# IoT_6LoWPAN_gateway_v01.net
KiCad netlist of a schematic drawn in Altium Designer
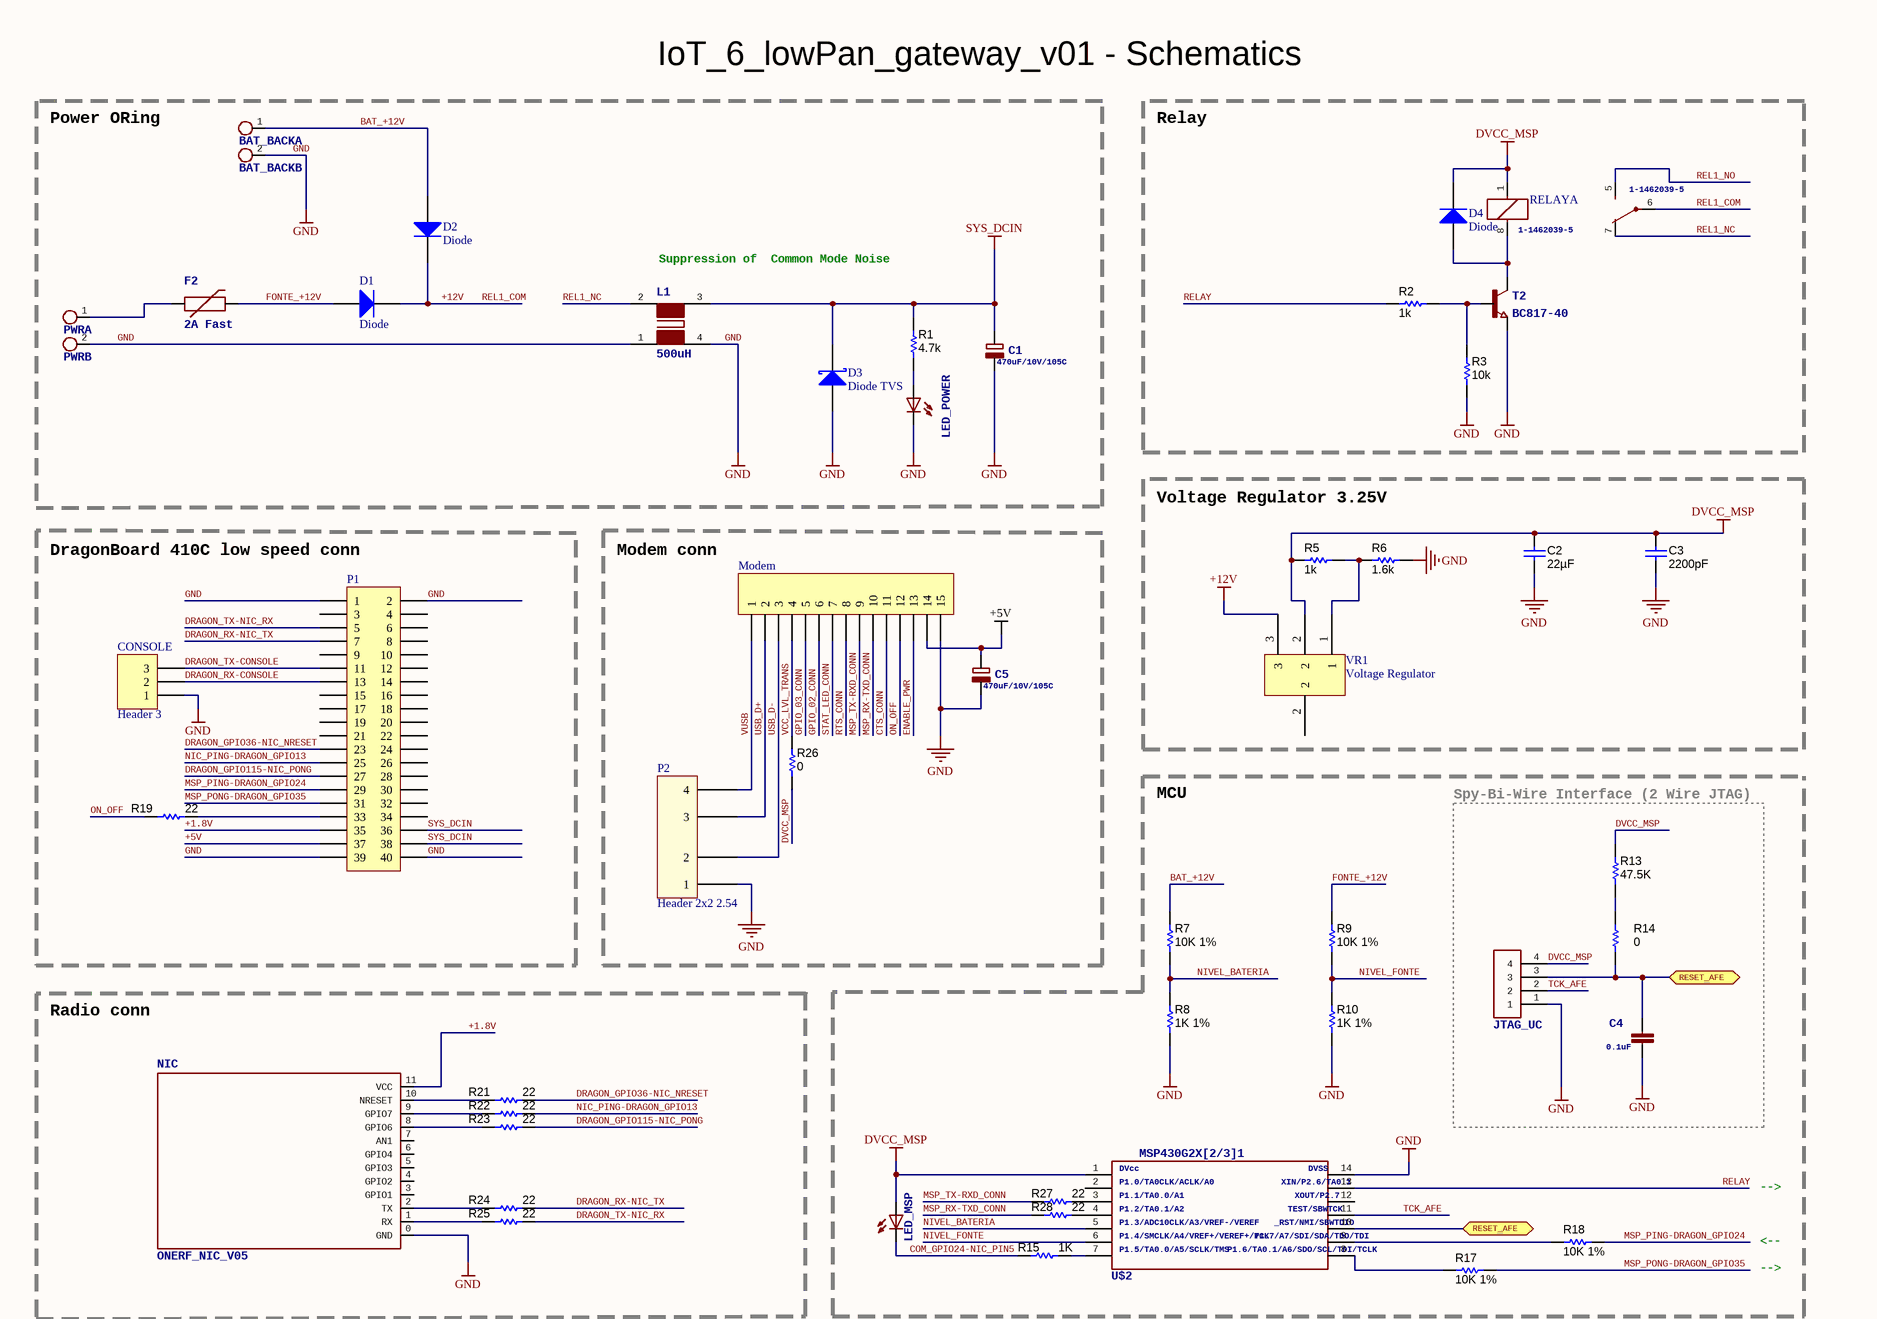
[diagram p0: IoT_6LoWPAN_gateway_v01.SchDoc, top]
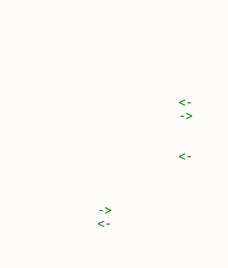
[diagram p1: IoT_6LoWPAN_gateway_v01.SchDoc, bottom]

(export (version "E")
  (design (tool "Eeschema 10.0.6"))
  (components
    (comp (ref "BAT_BACK")
      (value "MKDSN1,5/2-5,08")
      (footprint "MKDSN1,5/2-5,08")
      (libsource (lib "") (part "MKDSN1,5/2-5,08_1"))
    )
    (comp (ref "C1")
      (value "470uF/10V/105C")
      (footprint "E2,5-6,3")
      (description "POLARIZED CAPACITOR, European symbol")
      (libsource (lib "oneRF_Base_COM_v04") (part "CPOL-EUE2.5-6.3"))
    )
    (comp (ref "C2")
      (value "C2012X5R1C226K125AC")
      (footprint "0805_HV")
      (description "CAP, CERM, 22 µF, 16 V, +/- 10%, X5R, 0805")
      (fields (field (name "VALUEDISPLAYED") "22µF"))
      (libsource (lib "Capacitor_Ceramic") (part "C2012X5R1C226K125AC"))
    )
    (comp (ref "C3")
      (value "CL10B222KB8SFNC")
      (footprint "0603")
      (description "CAP, CERM, 2200 pF, 50 V, +/- 10%, X7R, 0603")
      (fields (field (name "VALUEDISPLAYED") "2200pF") (field (name "PUBLISHER") "Texas Instruments"))
      (libsource (lib "altium-import") (part "root_3_C1005X7R1H222K_"))
    )
    (comp (ref "C4")
      (value "0.1uF")
      (footprint "0603")
      (description "CAPACITOR, European symbol")
      (libsource (lib "rcl") (part "C-EUC0603_DWS"))
    )
    (comp (ref "C5")
      (value "470uF/10V/105C")
      (footprint "E2,5-6,3")
      (description "POLARIZED CAPACITOR, European symbol")
      (libsource (lib "oneRF_Base_COM_v04") (part "CPOL-EUE2.5-6.3"))
    )
    (comp (ref "CONSOLE")
      (value "Header 3")
      (footprint "HDR1X3")
      (description "Header, 3-Pin")
      (fields (field (name "PUBLISHER") "Altium Limited"))
      (libsource (lib "Miscellaneous Connectors") (part "Header 3"))
    )
    (comp (ref "D1")
      (value "Diode")
      (footprint "SOD-80")
      (description "Diode, 100v, 1V, 200mA, -65º, 175º, SMT")
      (fields (field (name "PARTNUMBER") "FDLL4148_D87Z"))
      (libsource (lib "Miscellaneous Devices") (part "Diode"))
    )
    (comp (ref "D2")
      (value "Diode")
      (footprint "SOD-80")
      (description "Diode, 100v, 1V, 200mA, -65º, 175º, SMT")
      (fields (field (name "PARTNUMBER") "FDLL4148_D87Z"))
      (libsource (lib "Miscellaneous Devices") (part "Diode"))
    )
    (comp (ref "D3")
      (value "Diode TVS")
      (footprint "SMB")
      (description "Schottky Diode")
      (fields (field (name "PUBLISHER") "Altium Limited"))
      (libsource (lib "Miscellaneous Devices") (part "D Schottky"))
    )
    (comp (ref "D4")
      (value "Diode")
      (footprint "SOD-80")
      (description "Diode, 100v, 1V, 200mA, -65º, 175º, SMT")
      (fields (field (name "PARTNUMBER") "FDLL4148_D87Z"))
      (libsource (lib "Miscellaneous Devices") (part "Diode"))
    )
    (comp (ref "F2")
      (value "2A Fast")
      (footprint "C1206")
      (description "Resettable Fuse PTCResettable Fuse. Spark Fun Electronics SKU : COM-08357")
      (libsource (lib "SparkFun-PowerIC") (part "PTCSMD-W"))
    )
    (comp (ref "JTAG_UC")
      (value "CONECTOR_1X042.54MM")
      (footprint "HDR1X4")
      (libsource (lib "sparkFun2") (part "CONECTOR_1X042.54MM"))
    )
    (comp (ref "L1")
      (value "500uH")
      (footprint "WE-SL2_74422...")
      (libsource (lib "qualified_1") (part "WE-SL2"))
    )
    (comp (ref "LED_MSP")
      (value "LED/WHITE/0603")
      (footprint "LED0603")
      (libsource (lib "Shield_Dragon") (part "LED0603_WWS"))
    )
    (comp (ref "LED_POWER")
      (value "LED/Red/0603")
      (footprint "LED0603")
      (libsource (lib "Shield_Dragon") (part "LED0603DWS"))
    )
    (comp (ref "Modem")
      (value "oneRF_Modem_v01")
      (footprint "oneRF_Modem_v01")
      (description "CONN HEADER .100\" SNGL STR 15POS")
      (fields
        (field (name "MANUFACTURER") "Wurth Electronics Inc.")
        (field (name "MANUFACTURER PART NUMBER") "61301511121")
      )
      (libsource (lib "Schlib1 - copy") (part "Header 15"))
    )
    (comp (ref "NIC")
      (value "ONERF_NIC_V05")
      (footprint "ONERF_NIC_V05")
      (libsource (lib "oneRF_Base_COM_v04") (part "ONERF_NIC_V05"))
    )
    (comp (ref "P1")
      (value "Header 20X2")
      (footprint "HDR2X20")
      (description "Header, 20-Pin, Dual row")
      (fields (field (name "PUBLISHER") "Altium Limited"))
      (libsource (lib "Miscellaneous Connectors") (part "Header 20X2"))
    )
    (comp (ref "P2")
      (value "Header 2x2 2.54")
      (footprint "HEADER2x2(2.54)")
      (libsource (lib "Shield_Dragon") (part "HEADER2x2(2.54)"))
    )
    (comp (ref "PWR")
      (value "MKDSN1,5/2-5,08")
      (footprint "MKDSN1,5/2-5,08")
      (libsource (lib "") (part "MKDSN1,5/2-5,08_1"))
    )
    (comp (ref "R1")
      (value "4.7k")
      (footprint "0603")
      (description "RES, 1kohm, 1%, 1/10W, 0603")
      (fields (field (name "PARTNUMBER") "CRCW06031K00FKEA"))
      (libsource (lib "MiscParts") (part "Resistor"))
    )
    (comp (ref "R2")
      (value "1k")
      (footprint "0603")
      (description "RES, 1kohm, 1%, 1/10W, 0603")
      (fields (field (name "PARTNUMBER") "CRCW06031K00FKEA"))
      (libsource (lib "MiscParts") (part "Resistor"))
    )
    (comp (ref "R3")
      (value "10k")
      (footprint "0603")
      (description "RES, 1kohm, 1%, 1/10W, 0603")
      (fields (field (name "PARTNUMBER") "CRCW06031K00FKEA"))
      (libsource (lib "MiscParts") (part "Resistor"))
    )
    (comp (ref "R5")
      (value "1k")
      (footprint "0603")
      (description "RES, 1kohm, 1%, 1/10W, 0603")
      (fields (field (name "PARTNUMBER") "CRCW06031K00FKEA"))
      (libsource (lib "MiscParts") (part "Resistor"))
    )
    (comp (ref "R6")
      (value "1.6k")
      (footprint "0603")
      (description "RES, 1.6kohm, 1%, 1/10W, 0603")
      (fields (field (name "PARTNUMBER") "RC0603FR-071K6L"))
      (libsource (lib "MiscParts") (part "Resistor"))
    )
    (comp (ref "R7")
      (value "10K 1%")
      (footprint "0603")
      (description "RES, 1kohm, 1%, 1/10W, 0603")
      (fields (field (name "PARTNUMBER") "CRCW06031K00FKEA"))
      (libsource (lib "MiscParts") (part "Resistor"))
    )
    (comp (ref "R8")
      (value "1K 1%")
      (footprint "0603")
      (description "RES, 1kohm, 1%, 1/10W, 0603")
      (fields (field (name "PARTNUMBER") "CRCW06031K00FKEA"))
      (libsource (lib "MiscParts") (part "Resistor"))
    )
    (comp (ref "R9")
      (value "10K 1%")
      (footprint "0603")
      (description "RES, 1kohm, 1%, 1/10W, 0603")
      (fields (field (name "PARTNUMBER") "CRCW06031K00FKEA"))
      (libsource (lib "MiscParts") (part "Resistor"))
    )
    (comp (ref "R10")
      (value "1K 1%")
      (footprint "0603")
      (description "RES, 1kohm, 1%, 1/10W, 0603")
      (fields (field (name "PARTNUMBER") "CRCW06031K00FKEA"))
      (libsource (lib "MiscParts") (part "Resistor"))
    )
    (comp (ref "R13")
      (value "47.5K")
      (footprint "0603")
      (description "RES, 1kohm, 1%, 1/10W, 0603")
      (fields (field (name "PARTNUMBER") "CRCW06031K00FKEA"))
      (libsource (lib "MiscParts") (part "Resistor"))
    )
    (comp (ref "R14")
      (value "0")
      (footprint "0603")
      (description "RES, 1kohm, 1%, 1/10W, 0603")
      (fields (field (name "PARTNUMBER") "CRCW06031K00FKEA"))
      (libsource (lib "MiscParts") (part "Resistor"))
    )
    (comp (ref "R15")
      (value "1K")
      (footprint "0603")
      (description "RES, 1kohm, 1%, 1/10W, 0603")
      (fields (field (name "PARTNUMBER") "CRCW06031K00FKEA"))
      (libsource (lib "MiscParts") (part "Resistor"))
    )
    (comp (ref "R17")
      (value "10K 1%")
      (footprint "0603")
      (description "RES, 1kohm, 1%, 1/10W, 0603")
      (fields (field (name "PARTNUMBER") "CRCW06031K00FKEA"))
      (libsource (lib "MiscParts") (part "Resistor"))
    )
    (comp (ref "R18")
      (value "10K 1%")
      (footprint "0603")
      (description "RES, 1kohm, 1%, 1/10W, 0603")
      (fields (field (name "PARTNUMBER") "CRCW06031K00FKEA"))
      (libsource (lib "MiscParts") (part "Resistor"))
    )
    (comp (ref "R19")
      (value "22")
      (footprint "0603")
      (description "RES, 1kohm, 1%, 1/10W, 0603")
      (fields (field (name "PARTNUMBER") "CRCW06031K00FKEA"))
      (libsource (lib "MiscParts") (part "Resistor"))
    )
    (comp (ref "R21")
      (value "22")
      (footprint "0603")
      (description "RES, 1kohm, 1%, 1/10W, 0603")
      (fields (field (name "PARTNUMBER") "CRCW06031K00FKEA"))
      (libsource (lib "MiscParts") (part "Resistor"))
    )
    (comp (ref "R22")
      (value "22")
      (footprint "0603")
      (description "RES, 1kohm, 1%, 1/10W, 0603")
      (fields (field (name "PARTNUMBER") "CRCW06031K00FKEA"))
      (libsource (lib "MiscParts") (part "Resistor"))
    )
    (comp (ref "R23")
      (value "22")
      (footprint "0603")
      (description "RES, 1kohm, 1%, 1/10W, 0603")
      (fields (field (name "PARTNUMBER") "CRCW06031K00FKEA"))
      (libsource (lib "MiscParts") (part "Resistor"))
    )
    (comp (ref "R24")
      (value "22")
      (footprint "0603")
      (description "RES, 1kohm, 1%, 1/10W, 0603")
      (fields (field (name "PARTNUMBER") "CRCW06031K00FKEA"))
      (libsource (lib "MiscParts") (part "Resistor"))
    )
    (comp (ref "R25")
      (value "22")
      (footprint "0603")
      (description "RES, 1kohm, 1%, 1/10W, 0603")
      (fields (field (name "PARTNUMBER") "CRCW06031K00FKEA"))
      (libsource (lib "MiscParts") (part "Resistor"))
    )
    (comp (ref "R26")
      (value "0")
      (footprint "0603")
      (description "RES, 1kohm, 1%, 1/10W, 0603")
      (fields (field (name "PARTNUMBER") "CRCW06031K00FKEA"))
      (libsource (lib "MiscParts") (part "Resistor"))
    )
    (comp (ref "R27")
      (value "22")
      (footprint "0603")
      (description "RES, 1kohm, 1%, 1/10W, 0603")
      (fields (field (name "PARTNUMBER") "CRCW06031K00FKEA"))
      (libsource (lib "MiscParts") (part "Resistor"))
    )
    (comp (ref "R28")
      (value "22")
      (footprint "0603")
      (description "RES, 1kohm, 1%, 1/10W, 0603")
      (fields (field (name "PARTNUMBER") "CRCW06031K00FKEA"))
      (libsource (lib "MiscParts") (part "Resistor"))
    )
    (comp (ref "RELAY")
      (value "1-1462039-5")
      (footprint "1-1462039-5")
      (description "RELAY")
      (libsource (lib "Shield_Dragon") (part "1-1462039-5"))
    )
    (comp (ref "T2")
      (value "BC817-40")
      (footprint "SOT23_N")
      (description "NPN TRANSISTOR")
      (libsource (lib "semicon-smd-ipc") (part "NPN-TRANSISTOR_SOT23"))
    )
    (comp (ref "U$2")
      (value "MSP430G2231")
      (footprint "PW014_N")
      (fields
        (field (name "MSP430G2X[2/3]1") "MSP430G2X[2/3]1")
        (field (name "DVCC") "DVcc")
        (field (name "P1.0/TA0CLK/ACLK/A0") "P1.0/TA0CLK/ACLK/A0")
        (field (name "P1.1/TA0.0/A1") "P1.1/TA0.0/A1")
        (field (name "P1.2/TA0.1/A2") "P1.2/TA0.1/A2")
        (field (name "P1.3/ADC10CLK/A3/VREF-/VEREF") "P1.3/ADC10CLK/A3/VREF-/VEREF")
        (field (name "P1.4/SMCLK/A4/VREF+/VEREF+/TCK") "P1.4/SMCLK/A4/VREF+/VEREF+/TCK")
        (field (name "P1.5/TA0.0/A5/SCLK/TMS") "P1.5/TA0.0/A5/SCLK/TMS")
        (field (name "P1.6/TA0.1/A6/SDO/SCL/TDI/TCLK") "P1.6/TA0.1/A6/SDO/SCL/TDI/TCLK")
        (field (name "P1.7/A7/SDI/SDA/TDO/TDI") "P1.7/A7/SDI/SDA/TDO/TDI")
        (field (name "_RST/NMI/SBWTDIO") "_RST/NMI/SBWTDIO")
        (field (name "TEST/SBWTCK") "TEST/SBWTCK")
        (field (name "XOUT/P2.7") "XOUT/P2.7")
        (field (name "XIN/P2.6/TA0.1") "XIN/P2.6/TA0.1")
        (field (name "DVSS") "DVSS")
      )
      (libsource (lib "TI_MSP430_v16") (part "G2X[2/3]1---PW14"))
    )
    (comp (ref "VR1")
      (value "Voltage Regulator")
      (footprint "SOT223")
      (fields (field (name "PARTNUMBER") "AZ1117H-ADJTRE1"))
      (libsource (lib "Shield_Dragon") (part "Voltage Regulator"))
    )
  )
  (nets
    (net (code "1") (name "+5V") (class "Default")
      (node (ref "C5") (pin "+") (pinfunction "+_+") (pintype "passive"))
      (node (ref "Modem") (pin "14") (pinfunction "14_14") (pintype "passive"))
      (node (ref "P1") (pin "37") (pinfunction "37_37") (pintype "passive"))
    )
    (net (code "2") (name "+12V") (class "Default")
      (node (ref "D1") (pin "2") (pinfunction "K_2") (pintype "passive"))
      (node (ref "D2") (pin "2") (pinfunction "K_2") (pintype "passive"))
      (node (ref "RELAY") (pin "6") (pinfunction "COM_6") (pintype "passive"))
      (node (ref "VR1") (pin "3") (pinfunction "3_3") (pintype "passive"))
    )
    (net (code "3") (name "/+1.8V") (class "Default")
      (node (ref "NIC") (pin "11") (pinfunction "VCC_11") (pintype "power_in"))
      (node (ref "P1") (pin "35") (pinfunction "35_35") (pintype "passive"))
    )
    (net (code "4") (name "/BAT_+12V") (class "Default")
      (node (ref "BAT_BACK") (pin "1") (pinfunction "KL_1") (pintype "passive"))
      (node (ref "D2") (pin "1") (pinfunction "A_1") (pintype "passive"))
      (node (ref "R7") (pin "2") (pinfunction "2_2") (pintype "passive"))
    )
    (net (code "5") (name "/COM_GPIO24-NIC_PIN5") (class "Default")
      (node (ref "LED_MSP") (pin "2") (pinfunction "C_2") (pintype "passive"))
      (node (ref "R15") (pin "2") (pinfunction "2_2") (pintype "passive"))
    )
    (net (code "6") (name "/CTS_CONN") (class "Default")
      (node (ref "Modem") (pin "11") (pinfunction "11_11") (pintype "passive"))
    )
    (net (code "7") (name "/DRAGON_GPIO36-NIC_NRESET") (class "Default")
      (node (ref "P1") (pin "23") (pinfunction "23_23") (pintype "passive"))
      (node (ref "R21") (pin "1") (pinfunction "1_1") (pintype "passive"))
    )
    (net (code "8") (name "/DRAGON_GPIO115-NIC_PONG") (class "Default")
      (node (ref "P1") (pin "27") (pinfunction "27_27") (pintype "passive"))
      (node (ref "R23") (pin "1") (pinfunction "1_1") (pintype "passive"))
    )
    (net (code "9") (name "/DRAGON_RX-CONSOLE") (class "Default")
      (node (ref "CONSOLE") (pin "2") (pinfunction "2_2") (pintype "passive"))
      (node (ref "P1") (pin "13") (pinfunction "13_13") (pintype "passive"))
    )
    (net (code "10") (name "/DRAGON_RX-NIC_TX") (class "Default")
      (node (ref "P1") (pin "7") (pinfunction "7_7") (pintype "passive"))
      (node (ref "R24") (pin "1") (pinfunction "1_1") (pintype "passive"))
    )
    (net (code "11") (name "/DRAGON_TX-CONSOLE") (class "Default")
      (node (ref "CONSOLE") (pin "3") (pinfunction "3_3") (pintype "passive"))
      (node (ref "P1") (pin "11") (pinfunction "11_11") (pintype "passive"))
    )
    (net (code "12") (name "/DRAGON_TX-NIC_RX") (class "Default")
      (node (ref "P1") (pin "5") (pinfunction "5_5") (pintype "passive"))
      (node (ref "R25") (pin "1") (pinfunction "1_1") (pintype "passive"))
    )
    (net (code "13") (name "/ENABLE_PWR") (class "Default")
      (node (ref "Modem") (pin "13") (pinfunction "13_13") (pintype "passive"))
    )
    (net (code "14") (name "/FONTE_+12V") (class "Default")
      (node (ref "D1") (pin "1") (pinfunction "A_1") (pintype "passive"))
      (node (ref "F2") (pin "2") (pinfunction "2_2") (pintype "passive"))
      (node (ref "R9") (pin "2") (pinfunction "2_2") (pintype "passive"))
    )
    (net (code "15") (name "/GPIO_02_CONN") (class "Default")
      (node (ref "Modem") (pin "6") (pinfunction "6_6") (pintype "passive"))
    )
    (net (code "16") (name "/GPIO_03_CONN") (class "Default")
      (node (ref "Modem") (pin "5") (pinfunction "5_5") (pintype "passive"))
    )
    (net (code "17") (name "/MSP_PING-DRAGON_GPIO24") (class "Default")
      (node (ref "P1") (pin "29") (pinfunction "29_29") (pintype "passive"))
      (node (ref "R18") (pin "1") (pinfunction "1_1") (pintype "passive"))
    )
    (net (code "18") (name "/MSP_PONG-DRAGON_GPIO35") (class "Default")
      (node (ref "P1") (pin "31") (pinfunction "31_31") (pintype "passive"))
      (node (ref "R17") (pin "1") (pinfunction "1_1") (pintype "passive"))
    )
    (net (code "19") (name "/MSP_RX-TXD_CONN") (class "Default")
      (node (ref "Modem") (pin "10") (pinfunction "10_10") (pintype "passive"))
      (node (ref "R28") (pin "2") (pinfunction "2_2") (pintype "passive"))
    )
    (net (code "20") (name "/MSP_TX-RXD_CONN") (class "Default")
      (node (ref "Modem") (pin "9") (pinfunction "9_9") (pintype "passive"))
      (node (ref "R27") (pin "2") (pinfunction "2_2") (pintype "passive"))
    )
    (net (code "21") (name "/NIC_PING-DRAGON_GPIO13") (class "Default")
      (node (ref "P1") (pin "25") (pinfunction "25_25") (pintype "passive"))
      (node (ref "R22") (pin "1") (pinfunction "1_1") (pintype "passive"))
    )
    (net (code "22") (name "/NIVEL_BATERIA") (class "Default")
      (node (ref "R7") (pin "1") (pinfunction "1_1") (pintype "passive"))
      (node (ref "R8") (pin "2") (pinfunction "2_2") (pintype "passive"))
      (node (ref "U$2") (pin "5") (pinfunction "5_5") (pintype "passive"))
    )
    (net (code "23") (name "/NIVEL_FONTE") (class "Default")
      (node (ref "R10") (pin "2") (pinfunction "2_2") (pintype "passive"))
      (node (ref "R9") (pin "1") (pinfunction "1_1") (pintype "passive"))
      (node (ref "U$2") (pin "6") (pinfunction "6_6") (pintype "passive"))
    )
    (net (code "24") (name "/ON_OFF") (class "Default")
      (node (ref "Modem") (pin "12") (pinfunction "12_12") (pintype "passive"))
      (node (ref "R19") (pin "2") (pinfunction "2_2") (pintype "passive"))
    )
    (net (code "25") (name "/REL1_NC") (class "Default")
      (node (ref "L1") (pin "2") (pinfunction "1_2") (pintype "passive"))
      (node (ref "RELAY") (pin "7") (pinfunction "NC_7") (pintype "passive"))
    )
    (net (code "26") (name "/REL1_NO") (class "Default")
      (node (ref "RELAY") (pin "5") (pinfunction "NO_5") (pintype "passive"))
    )
    (net (code "27") (name "/RELAY") (class "Default")
      (node (ref "R2") (pin "2") (pinfunction "2_2") (pintype "passive"))
      (node (ref "U$2") (pin "13") (pinfunction "13_13") (pintype "passive"))
    )
    (net (code "28") (name "/RESET_AFE") (class "Default")
      (node (ref "C4") (pin "1") (pinfunction "1_1") (pintype "passive"))
      (node (ref "JTAG_UC") (pin "3") (pinfunction "3_3") (pintype "passive"))
      (node (ref "R14") (pin "1") (pinfunction "1_1") (pintype "passive"))
      (node (ref "U$2") (pin "10") (pinfunction "10_10") (pintype "passive"))
    )
    (net (code "29") (name "/RTS_CONN") (class "Default")
      (node (ref "Modem") (pin "8") (pinfunction "8_8") (pintype "passive"))
    )
    (net (code "30") (name "/STAT_LED_CONN") (class "Default")
      (node (ref "Modem") (pin "7") (pinfunction "7_7") (pintype "passive"))
    )
    (net (code "31") (name "/TCK_AFE") (class "Default")
      (node (ref "JTAG_UC") (pin "2") (pinfunction "2_2") (pintype "passive"))
      (node (ref "U$2") (pin "11") (pinfunction "11_11") (pintype "passive"))
    )
    (net (code "32") (name "/USB_D+") (class "Default")
      (node (ref "Modem") (pin "2") (pinfunction "2_2") (pintype "passive"))
      (node (ref "P2") (pin "3") (pinfunction "3_3") (pintype "passive"))
    )
    (net (code "33") (name "/USB_D-") (class "Default")
      (node (ref "Modem") (pin "3") (pinfunction "3_3") (pintype "passive"))
      (node (ref "P2") (pin "2") (pinfunction "2_2") (pintype "passive"))
    )
    (net (code "34") (name "/VCC_LVL_TRANS") (class "Default")
      (node (ref "Modem") (pin "4") (pinfunction "4_4") (pintype "passive"))
      (node (ref "R26") (pin "2") (pinfunction "2_2") (pintype "passive"))
    )
    (net (code "35") (name "/VUSB") (class "Default")
      (node (ref "Modem") (pin "1") (pinfunction "1_1") (pintype "passive"))
      (node (ref "P2") (pin "4") (pinfunction "4_4") (pintype "passive"))
    )
    (net (code "36") (name "DVCC_MSP") (class "Default")
      (node (ref "C2") (pin "1") (pinfunction "1_1") (pintype "passive"))
      (node (ref "C3") (pin "2") (pinfunction "2_2") (pintype "passive"))
      (node (ref "D4") (pin "2") (pinfunction "K_2") (pintype "passive"))
      (node (ref "JTAG_UC") (pin "4") (pinfunction "4_4") (pintype "passive"))
      (node (ref "LED_MSP") (pin "1") (pinfunction "A_1") (pintype "passive"))
      (node (ref "R13") (pin "2") (pinfunction "2_2") (pintype "passive"))
      (node (ref "R26") (pin "1") (pinfunction "1_1") (pintype "passive"))
      (node (ref "R5") (pin "1") (pinfunction "1_1") (pintype "passive"))
      (node (ref "RELAY") (pin "1") (pinfunction "1_1") (pintype "passive"))
      (node (ref "U$2") (pin "1") (pinfunction "1_1") (pintype "passive"))
      (node (ref "VR1") (pin "2") (pinfunction "2_2") (pintype "passive"))
    )
    (net (code "37") (name "GND") (class "Default")
      (node (ref "BAT_BACK") (pin "2") (pinfunction "KL_2") (pintype "passive"))
      (node (ref "C1") (pin "-") (pinfunction "-_-") (pintype "passive"))
      (node (ref "C2") (pin "2") (pinfunction "2_2") (pintype "passive"))
      (node (ref "C3") (pin "1") (pinfunction "1_1") (pintype "passive"))
      (node (ref "C4") (pin "2") (pinfunction "2_2") (pintype "passive"))
      (node (ref "C5") (pin "-") (pinfunction "-_-") (pintype "passive"))
      (node (ref "CONSOLE") (pin "1") (pinfunction "1_1") (pintype "passive"))
      (node (ref "D3") (pin "1") (pinfunction "A_1") (pintype "passive"))
      (node (ref "JTAG_UC") (pin "1") (pinfunction "1_1") (pintype "passive"))
      (node (ref "L1") (pin "1") (pinfunction "2_1") (pintype "passive"))
      (node (ref "L1") (pin "4") (pinfunction "3_4") (pintype "passive"))
      (node (ref "LED_POWER") (pin "2") (pinfunction "C_2") (pintype "passive"))
      (node (ref "Modem") (pin "15") (pinfunction "15_15") (pintype "passive"))
      (node (ref "NIC") (pin "0") (pinfunction "GND_0") (pintype "power_in"))
      (node (ref "P1") (pin "1") (pinfunction "1_1") (pintype "passive"))
      (node (ref "P1") (pin "2") (pinfunction "2_2") (pintype "passive"))
      (node (ref "P1") (pin "39") (pinfunction "39_39") (pintype "passive"))
      (node (ref "P1") (pin "40") (pinfunction "40_40") (pintype "passive"))
      (node (ref "P2") (pin "1") (pinfunction "1_1") (pintype "passive"))
      (node (ref "PWR") (pin "2") (pinfunction "KL_2") (pintype "passive"))
      (node (ref "R10") (pin "1") (pinfunction "1_1") (pintype "passive"))
      (node (ref "R3") (pin "1") (pinfunction "1_1") (pintype "passive"))
      (node (ref "R6") (pin "2") (pinfunction "2_2") (pintype "passive"))
      (node (ref "R8") (pin "1") (pinfunction "1_1") (pintype "passive"))
      (node (ref "T2") (pin "2") (pinfunction "E_2") (pintype "passive"))
      (node (ref "U$2") (pin "14") (pinfunction "14_14") (pintype "passive"))
    )
    (net (code "38") (name "Net-(D4-A)") (class "Default")
      (node (ref "D4") (pin "1") (pinfunction "A_1") (pintype "passive"))
      (node (ref "RELAY") (pin "8") (pinfunction "8_8") (pintype "passive"))
      (node (ref "T2") (pin "3") (pinfunction "C_3") (pintype "passive"))
    )
    (net (code "39") (name "Net-(LED_POWER-A)") (class "Default")
      (node (ref "LED_POWER") (pin "1") (pinfunction "A_1") (pintype "passive"))
      (node (ref "R1") (pin "1") (pinfunction "1_1") (pintype "passive"))
    )
    (net (code "40") (name "Net-(NIC-GPIO6)") (class "Default")
      (node (ref "NIC") (pin "8") (pinfunction "GPIO6_8") (pintype "passive"))
      (node (ref "R23") (pin "2") (pinfunction "2_2") (pintype "passive"))
    )
    (net (code "41") (name "Net-(NIC-GPIO7)") (class "Default")
      (node (ref "NIC") (pin "9") (pinfunction "GPIO7_9") (pintype "passive"))
      (node (ref "R22") (pin "2") (pinfunction "2_2") (pintype "passive"))
    )
    (net (code "42") (name "Net-(NIC-NRESET)") (class "Default")
      (node (ref "NIC") (pin "10") (pinfunction "NRESET_10") (pintype "passive"))
      (node (ref "R21") (pin "2") (pinfunction "2_2") (pintype "passive"))
    )
    (net (code "43") (name "Net-(NIC-RX)") (class "Default")
      (node (ref "NIC") (pin "1") (pinfunction "RX_1") (pintype "passive"))
      (node (ref "R25") (pin "2") (pinfunction "2_2") (pintype "passive"))
    )
    (net (code "44") (name "Net-(NIC-TX)") (class "Default")
      (node (ref "NIC") (pin "2") (pinfunction "TX_2") (pintype "passive"))
      (node (ref "R24") (pin "2") (pinfunction "2_2") (pintype "passive"))
    )
    (net (code "45") (name "Net-(P1-Pad33)") (class "Default")
      (node (ref "P1") (pin "33") (pinfunction "33_33") (pintype "passive"))
      (node (ref "R19") (pin "1") (pinfunction "1_1") (pintype "passive"))
    )
    (net (code "46") (name "Net-(PWRA-KL)") (class "Default")
      (node (ref "F2") (pin "1") (pinfunction "1_1") (pintype "passive"))
      (node (ref "PWR") (pin "1") (pinfunction "KL_1") (pintype "passive"))
    )
    (net (code "47") (name "Net-(R5-Pad2)") (class "Default")
      (node (ref "R5") (pin "2") (pinfunction "2_2") (pintype "passive"))
      (node (ref "R6") (pin "1") (pinfunction "1_1") (pintype "passive"))
      (node (ref "VR1") (pin "1") (pinfunction "1_1") (pintype "passive"))
    )
    (net (code "48") (name "Net-(R13-Pad1)") (class "Default")
      (node (ref "R13") (pin "1") (pinfunction "1_1") (pintype "passive"))
      (node (ref "R14") (pin "2") (pinfunction "2_2") (pintype "passive"))
    )
    (net (code "49") (name "Net-(R15-Pad1)") (class "Default")
      (node (ref "R15") (pin "1") (pinfunction "1_1") (pintype "passive"))
      (node (ref "U$2") (pin "7") (pinfunction "7_7") (pintype "passive"))
    )
    (net (code "50") (name "Net-(R17-Pad2)") (class "Default")
      (node (ref "R17") (pin "2") (pinfunction "2_2") (pintype "passive"))
      (node (ref "U$2") (pin "8") (pinfunction "8_8") (pintype "passive"))
    )
    (net (code "51") (name "Net-(R18-Pad2)") (class "Default")
      (node (ref "R18") (pin "2") (pinfunction "2_2") (pintype "passive"))
      (node (ref "U$2") (pin "9") (pinfunction "9_9") (pintype "passive"))
    )
    (net (code "52") (name "Net-(R27-Pad1)") (class "Default")
      (node (ref "R27") (pin "1") (pinfunction "1_1") (pintype "passive"))
      (node (ref "U$2") (pin "3") (pinfunction "3_3") (pintype "passive"))
    )
    (net (code "53") (name "Net-(R28-Pad1)") (class "Default")
      (node (ref "R28") (pin "1") (pinfunction "1_1") (pintype "passive"))
      (node (ref "U$2") (pin "4") (pinfunction "4_4") (pintype "passive"))
    )
    (net (code "54") (name "Net-(T2-B)") (class "Default")
      (node (ref "R2") (pin "1") (pinfunction "1_1") (pintype "passive"))
      (node (ref "R3") (pin "2") (pinfunction "2_2") (pintype "passive"))
      (node (ref "T2") (pin "1") (pinfunction "B_1") (pintype "passive"))
    )
    (net (code "55") (name "SYS_DCIN") (class "Default")
      (node (ref "C1") (pin "+") (pinfunction "+_+") (pintype "passive"))
      (node (ref "D3") (pin "2") (pinfunction "K_2") (pintype "passive"))
      (node (ref "L1") (pin "3") (pinfunction "4_3") (pintype "passive"))
      (node (ref "P1") (pin "36") (pinfunction "36_36") (pintype "passive"))
      (node (ref "P1") (pin "38") (pinfunction "38_38") (pintype "passive"))
      (node (ref "R1") (pin "2") (pinfunction "2_2") (pintype "passive"))
    )
    (net (code "56") (name "unconnected-(NIC-AN1-Pad7)") (class "Default")
      (node (ref "NIC") (pin "7") (pinfunction "AN1_7") (pintype "passive"))
    )
    (net (code "57") (name "unconnected-(NIC-GPIO1-Pad3)") (class "Default")
      (node (ref "NIC") (pin "3") (pinfunction "GPIO1_3") (pintype "passive"))
    )
    (net (code "58") (name "unconnected-(NIC-GPIO2-Pad4)") (class "Default")
      (node (ref "NIC") (pin "4") (pinfunction "GPIO2_4") (pintype "passive"))
    )
    (net (code "59") (name "unconnected-(NIC-GPIO3-Pad5)") (class "Default")
      (node (ref "NIC") (pin "5") (pinfunction "GPIO3_5") (pintype "passive"))
    )
    (net (code "60") (name "unconnected-(NIC-GPIO4-Pad6)") (class "Default")
      (node (ref "NIC") (pin "6") (pinfunction "GPIO4_6") (pintype "passive"))
    )
    (net (code "61") (name "unconnected-(P1-Pad3)") (class "Default")
      (node (ref "P1") (pin "3") (pinfunction "3_3") (pintype "passive"))
    )
    (net (code "62") (name "unconnected-(P1-Pad4)") (class "Default")
      (node (ref "P1") (pin "4") (pinfunction "4_4") (pintype "passive"))
    )
    (net (code "63") (name "unconnected-(P1-Pad6)") (class "Default")
      (node (ref "P1") (pin "6") (pinfunction "6_6") (pintype "passive"))
    )
    (net (code "64") (name "unconnected-(P1-Pad8)") (class "Default")
      (node (ref "P1") (pin "8") (pinfunction "8_8") (pintype "passive"))
    )
    (net (code "65") (name "unconnected-(P1-Pad9)") (class "Default")
      (node (ref "P1") (pin "9") (pinfunction "9_9") (pintype "passive"))
    )
    (net (code "66") (name "unconnected-(P1-Pad10)") (class "Default")
      (node (ref "P1") (pin "10") (pinfunction "10_10") (pintype "passive"))
    )
    (net (code "67") (name "unconnected-(P1-Pad12)") (class "Default")
      (node (ref "P1") (pin "12") (pinfunction "12_12") (pintype "passive"))
    )
    (net (code "68") (name "unconnected-(P1-Pad14)") (class "Default")
      (node (ref "P1") (pin "14") (pinfunction "14_14") (pintype "passive"))
    )
    (net (code "69") (name "unconnected-(P1-Pad15)") (class "Default")
      (node (ref "P1") (pin "15") (pinfunction "15_15") (pintype "passive"))
    )
    (net (code "70") (name "unconnected-(P1-Pad16)") (class "Default")
      (node (ref "P1") (pin "16") (pinfunction "16_16") (pintype "passive"))
    )
    (net (code "71") (name "unconnected-(P1-Pad17)") (class "Default")
      (node (ref "P1") (pin "17") (pinfunction "17_17") (pintype "passive"))
    )
    (net (code "72") (name "unconnected-(P1-Pad18)") (class "Default")
      (node (ref "P1") (pin "18") (pinfunction "18_18") (pintype "passive"))
    )
    (net (code "73") (name "unconnected-(P1-Pad19)") (class "Default")
      (node (ref "P1") (pin "19") (pinfunction "19_19") (pintype "passive"))
    )
    (net (code "74") (name "unconnected-(P1-Pad20)") (class "Default")
      (node (ref "P1") (pin "20") (pinfunction "20_20") (pintype "passive"))
    )
    (net (code "75") (name "unconnected-(P1-Pad21)") (class "Default")
      (node (ref "P1") (pin "21") (pinfunction "21_21") (pintype "passive"))
    )
    (net (code "76") (name "unconnected-(P1-Pad22)") (class "Default")
      (node (ref "P1") (pin "22") (pinfunction "22_22") (pintype "passive"))
    )
    (net (code "77") (name "unconnected-(P1-Pad24)") (class "Default")
      (node (ref "P1") (pin "24") (pinfunction "24_24") (pintype "passive"))
    )
    (net (code "78") (name "unconnected-(P1-Pad26)") (class "Default")
      (node (ref "P1") (pin "26") (pinfunction "26_26") (pintype "passive"))
    )
    (net (code "79") (name "unconnected-(P1-Pad28)") (class "Default")
      (node (ref "P1") (pin "28") (pinfunction "28_28") (pintype "passive"))
    )
    (net (code "80") (name "unconnected-(P1-Pad30)") (class "Default")
      (node (ref "P1") (pin "30") (pinfunction "30_30") (pintype "passive"))
    )
    (net (code "81") (name "unconnected-(P1-Pad32)") (class "Default")
      (node (ref "P1") (pin "32") (pinfunction "32_32") (pintype "passive"))
    )
    (net (code "82") (name "unconnected-(P1-Pad34)") (class "Default")
      (node (ref "P1") (pin "34") (pinfunction "34_34") (pintype "passive"))
    )
    (net (code "83") (name "unconnected-(U$2-Pad2)") (class "Default")
      (node (ref "U$2") (pin "2") (pinfunction "2_2") (pintype "passive"))
    )
    (net (code "84") (name "unconnected-(U$2-Pad12)") (class "Default")
      (node (ref "U$2") (pin "12") (pinfunction "12_12") (pintype "passive"))
    )
    (net (code "85") (name "unconnected-(VR1-Pad2)") (class "Default")
      (node (ref "VR1") (pin "2") (pinfunction "2_2") (pintype "passive"))
    )
  )
)
